# lab1_kuchenov_usb_spi.net
KiCad netlist of a schematic drawn in Altium Designer
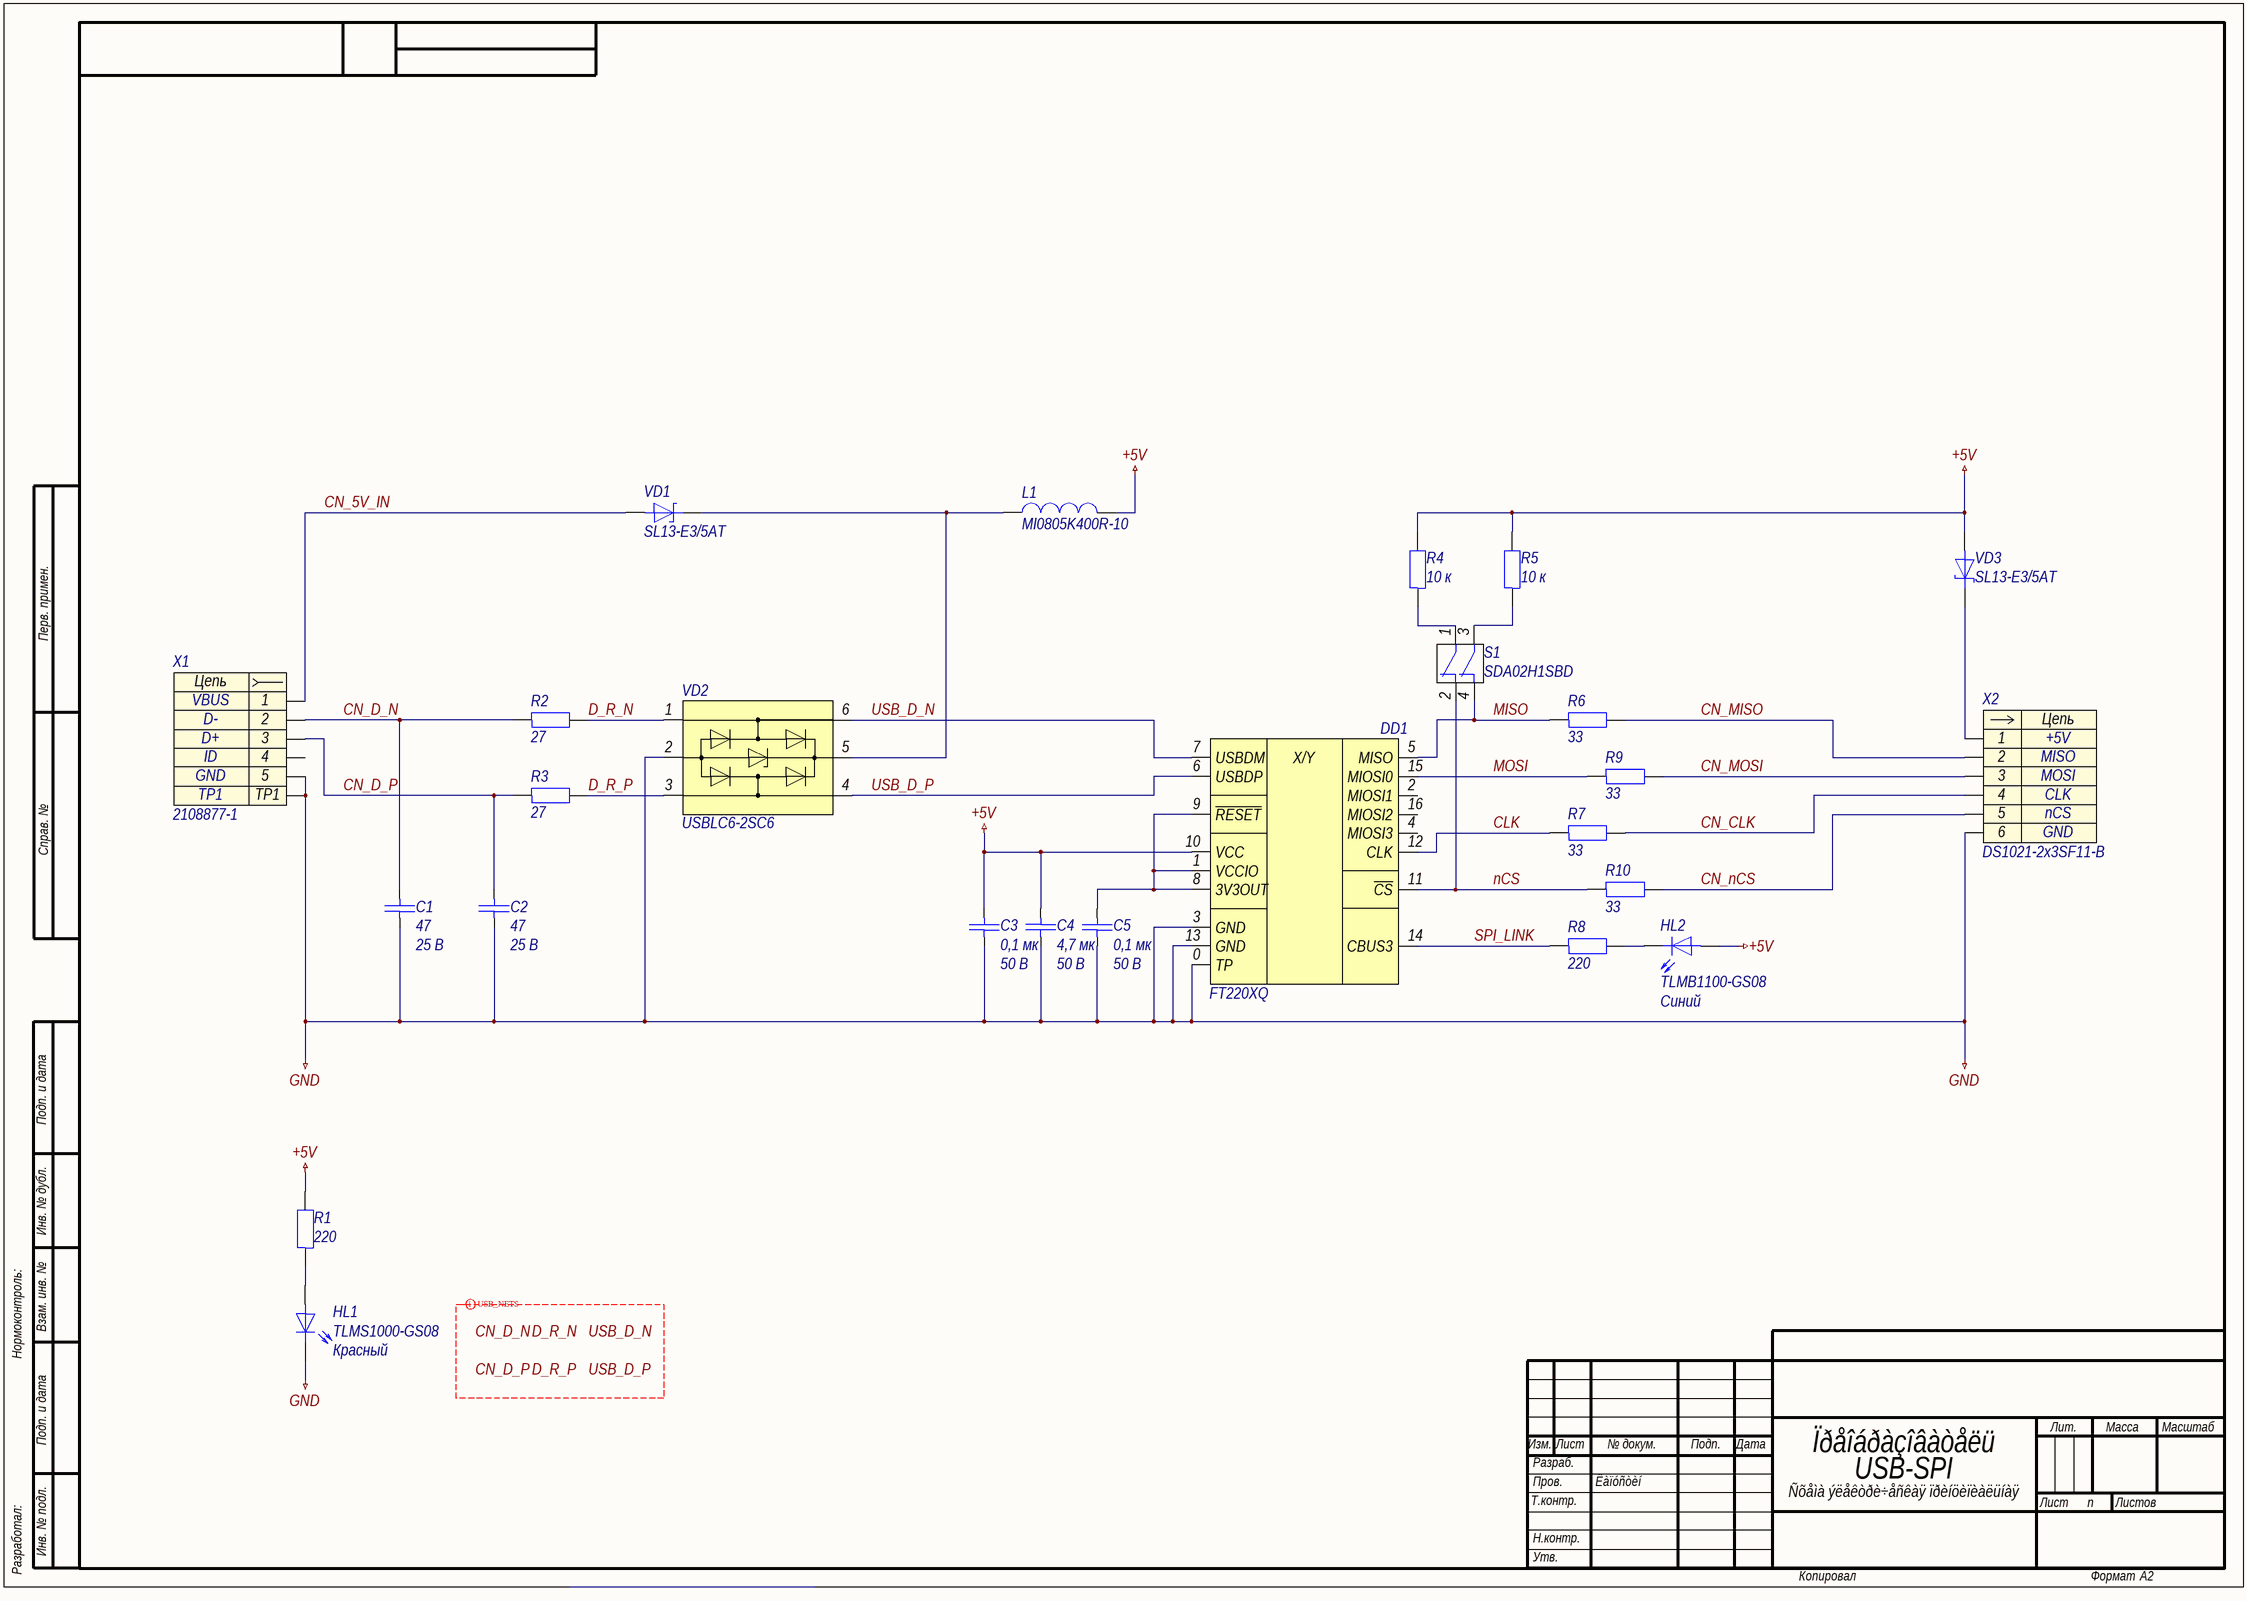
[diagram p0: lab1_kuchenov_usb_spi.SchDoc]

(export (version "E")
  (design (tool "Eeschema 10.0.6"))
  (components
    (comp (ref "C1")
      (value "47")
      (footprint "C0201")
      (description "=Описание")
      (fields (field (name "НАПРЯЖЕНИЕ") "25 В"))
      (libsource (lib "Database_Students") (part "CAPACITOR-NONPOLAR"))
    )
    (comp (ref "C2")
      (value "47")
      (footprint "C0201")
      (description "=Описание")
      (fields (field (name "НАПРЯЖЕНИЕ") "25 В"))
      (libsource (lib "Database_Students") (part "CAPACITOR-NONPOLAR"))
    )
    (comp (ref "C3")
      (value "0,1 мк")
      (footprint "C0603")
      (description "=Описание")
      (fields (field (name "НАПРЯЖЕНИЕ") "50 В"))
      (libsource (lib "Database_Students") (part "CAPACITOR-NONPOLAR"))
    )
    (comp (ref "C4")
      (value "4,7 мк")
      (footprint "C0805")
      (description "=Описание")
      (fields (field (name "НАПРЯЖЕНИЕ") "50 В"))
      (libsource (lib "Database_Students") (part "CAPACITOR-NONPOLAR"))
    )
    (comp (ref "C5")
      (value "0,1 мк")
      (footprint "C0603")
      (description "=Описание")
      (fields (field (name "НАПРЯЖЕНИЕ") "50 В"))
      (libsource (lib "Database_Students") (part "CAPACITOR-NONPOLAR"))
    )
    (comp (ref "DD1")
      (value "FT220XQ")
      (footprint "QFN-16-400X400X90")
      (description "=Описание")
      (libsource (lib "Database_Students") (part "FT220XQ"))
    )
    (comp (ref "HL1")
      (value "TLMS1000-GS08")
      (footprint "HL0603")
      (description "=Описание")
      (fields (field (name "COLOUR") "Красный"))
      (libsource (lib "Database_Students") (part "LED-COMMON"))
    )
    (comp (ref "HL2")
      (value "TLMB1100-GS08")
      (footprint "HL0603")
      (description "=Описание")
      (fields (field (name "COLOUR") "Синий"))
      (libsource (lib "Database_Students") (part "LED-COMMON"))
    )
    (comp (ref "L1")
      (value "MI0805K400R-10")
      (footprint "MI-2-0805")
      (description "=Описание")
      (libsource (lib "Database_Students") (part "FERRITE-BEAD"))
    )
    (comp (ref "R1")
      (value "220")
      (footprint "R0603")
      (description "=Описание")
      (libsource (lib "Database_Students") (part "R-COMMON"))
    )
    (comp (ref "R2")
      (value "27")
      (footprint "R0603")
      (description "=Описание")
      (libsource (lib "Database_Students") (part "R-COMMON"))
    )
    (comp (ref "R3")
      (value "27")
      (footprint "R0603")
      (description "=Описание")
      (libsource (lib "Database_Students") (part "R-COMMON"))
    )
    (comp (ref "R4")
      (value "10 к")
      (footprint "R0603")
      (description "=Описание")
      (libsource (lib "Database_Students") (part "R-COMMON"))
    )
    (comp (ref "R5")
      (value "10 к")
      (footprint "R0603")
      (description "=Описание")
      (libsource (lib "Database_Students") (part "R-COMMON"))
    )
    (comp (ref "R6")
      (value "33")
      (footprint "R0603")
      (description "=Описание")
      (libsource (lib "Database_Students") (part "R-COMMON"))
    )
    (comp (ref "R7")
      (value "33")
      (footprint "R0603")
      (description "=Описание")
      (libsource (lib "Database_Students") (part "R-COMMON"))
    )
    (comp (ref "R8")
      (value "220")
      (footprint "R0603")
      (description "=Описание")
      (libsource (lib "Database_Students") (part "R-COMMON"))
    )
    (comp (ref "R9")
      (value "33")
      (footprint "R0603")
      (description "=Описание")
      (libsource (lib "Database_Students") (part "R-COMMON"))
    )
    (comp (ref "R10")
      (value "33")
      (footprint "R0603")
      (description "=Описание")
      (libsource (lib "Database_Students") (part "R-COMMON"))
    )
    (comp (ref "S1")
      (value "SDA02H1SBD")
      (footprint "SDA02H1SBD")
      (description "=Описание")
      (libsource (lib "Database_Students") (part "SWITCH-4C"))
    )
    (comp (ref "VD1")
      (value "SL13-E3/5AT")
      (footprint "DO-214AC")
      (description "=Описание")
      (libsource (lib "Database_Students") (part "DIODE-SCHOTTKY"))
    )
    (comp (ref "VD2")
      (value "USBLC6-2SC6")
      (footprint "SOT23-6L")
      (description "=Описание")
      (libsource (lib "Database_Students") (part "USBLC6-2SC6"))
    )
    (comp (ref "VD3")
      (value "SL13-E3/5AT")
      (footprint "DO-214AC")
      (description "=Описание")
      (libsource (lib "Database_Students") (part "DIODE-SCHOTTKY"))
    )
    (comp (ref "X1")
      (value "2108877-1")
      (footprint "2108877-1")
      (libsource (lib "Database_Students") (part "HEADER-5-TP1-SCT"))
    )
    (comp (ref "X2")
      (value "DS1021-2x3SF11-B")
      (footprint "DS1021-2X3SF11-B")
      (description "=Описание")
      (libsource (lib "Database_Students") (part "HEADER-6-PLG"))
    )
  )
  (nets
    (net (code "1") (name "+5V") (class "Default")
      (node (ref "C3") (pin "1") (pinfunction "1_1") (pintype "passive"))
      (node (ref "C4") (pin "2") (pinfunction "2_2") (pintype "passive"))
      (node (ref "DD1") (pin "10") (pinfunction "VCC_10") (pintype "passive"))
      (node (ref "HL2") (pin "2") (pinfunction "2_2") (pintype "passive"))
      (node (ref "L1") (pin "2") (pinfunction "2_2") (pintype "passive"))
      (node (ref "R1") (pin "2") (pinfunction "2_2") (pintype "passive"))
      (node (ref "R4") (pin "2") (pinfunction "2_2") (pintype "passive"))
      (node (ref "R5") (pin "2") (pinfunction "2_2") (pintype "passive"))
      (node (ref "VD3") (pin "2") (pinfunction "2_2") (pintype "passive"))
    )
    (net (code "2") (name "/CLK") (class "Default")
      (node (ref "DD1") (pin "12") (pinfunction "CLK_12") (pintype "passive"))
      (node (ref "R7") (pin "1") (pinfunction "1_1") (pintype "passive"))
    )
    (net (code "3") (name "/CN_5V_IN") (class "Default")
      (node (ref "VD1") (pin "2") (pinfunction "2_2") (pintype "passive"))
      (node (ref "X1") (pin "1") (pinfunction "1_1") (pintype "passive"))
    )
    (net (code "4") (name "/CN_CLK") (class "Default")
      (node (ref "R7") (pin "2") (pinfunction "2_2") (pintype "passive"))
      (node (ref "X2") (pin "4") (pinfunction "4_4") (pintype "passive"))
    )
    (net (code "5") (name "/CN_D_N") (class "Default")
      (node (ref "C1") (pin "1") (pinfunction "1_1") (pintype "passive"))
      (node (ref "R2") (pin "1") (pinfunction "1_1") (pintype "passive"))
      (node (ref "X1") (pin "2") (pinfunction "2_2") (pintype "passive"))
    )
    (net (code "6") (name "/CN_D_P") (class "Default")
      (node (ref "C2") (pin "1") (pinfunction "1_1") (pintype "passive"))
      (node (ref "R3") (pin "1") (pinfunction "1_1") (pintype "passive"))
      (node (ref "X1") (pin "3") (pinfunction "3_3") (pintype "passive"))
    )
    (net (code "7") (name "/CN_MISO") (class "Default")
      (node (ref "R6") (pin "2") (pinfunction "2_2") (pintype "passive"))
      (node (ref "X2") (pin "2") (pinfunction "2_2") (pintype "passive"))
    )
    (net (code "8") (name "/CN_MOSI") (class "Default")
      (node (ref "R9") (pin "2") (pinfunction "2_2") (pintype "passive"))
      (node (ref "X2") (pin "3") (pinfunction "3_3") (pintype "passive"))
    )
    (net (code "9") (name "/CN_nCS") (class "Default")
      (node (ref "R10") (pin "2") (pinfunction "2_2") (pintype "passive"))
      (node (ref "X2") (pin "5") (pinfunction "5_5") (pintype "passive"))
    )
    (net (code "10") (name "/D_R_N") (class "Default")
      (node (ref "R2") (pin "2") (pinfunction "2_2") (pintype "passive"))
      (node (ref "VD2") (pin "1") (pinfunction "1_1") (pintype "passive"))
    )
    (net (code "11") (name "/D_R_P") (class "Default")
      (node (ref "R3") (pin "2") (pinfunction "2_2") (pintype "passive"))
      (node (ref "VD2") (pin "3") (pinfunction "3_3") (pintype "passive"))
    )
    (net (code "12") (name "/MISO") (class "Default")
      (node (ref "DD1") (pin "5") (pinfunction "MISO_5") (pintype "passive"))
      (node (ref "R6") (pin "1") (pinfunction "1_1") (pintype "passive"))
      (node (ref "S1") (pin "4") (pinfunction "4_4") (pintype "passive"))
    )
    (net (code "13") (name "/MOSI") (class "Default")
      (node (ref "DD1") (pin "15") (pinfunction "MIOSI0_15") (pintype "passive"))
      (node (ref "R9") (pin "1") (pinfunction "1_1") (pintype "passive"))
    )
    (net (code "14") (name "/SPI_LINK") (class "Default")
      (node (ref "DD1") (pin "14") (pinfunction "CBUS3_14") (pintype "passive"))
      (node (ref "R8") (pin "1") (pinfunction "1_1") (pintype "passive"))
    )
    (net (code "15") (name "/USB_D_N") (class "Default")
      (node (ref "DD1") (pin "7") (pinfunction "USBDM_7") (pintype "passive"))
      (node (ref "VD2") (pin "6") (pinfunction "6_6") (pintype "passive"))
    )
    (net (code "16") (name "/USB_D_P") (class "Default")
      (node (ref "DD1") (pin "6") (pinfunction "USBDP_6") (pintype "passive"))
      (node (ref "VD2") (pin "4") (pinfunction "4_4") (pintype "passive"))
    )
    (net (code "17") (name "/nCS") (class "Default")
      (node (ref "DD1") (pin "11") (pinfunction "~{CS}_11") (pintype "passive"))
      (node (ref "R10") (pin "1") (pinfunction "1_1") (pintype "passive"))
      (node (ref "S1") (pin "2") (pinfunction "2_2") (pintype "passive"))
    )
    (net (code "18") (name "GND") (class "Default")
      (node (ref "C1") (pin "2") (pinfunction "2_2") (pintype "passive"))
      (node (ref "C2") (pin "2") (pinfunction "2_2") (pintype "passive"))
      (node (ref "C3") (pin "2") (pinfunction "2_2") (pintype "passive"))
      (node (ref "C4") (pin "1") (pinfunction "1_1") (pintype "passive"))
      (node (ref "C5") (pin "2") (pinfunction "2_2") (pintype "passive"))
      (node (ref "DD1") (pin "0") (pinfunction "TP_0") (pintype "passive"))
      (node (ref "DD1") (pin "13") (pinfunction "GND_13") (pintype "passive"))
      (node (ref "DD1") (pin "3") (pinfunction "GND_3") (pintype "passive"))
      (node (ref "HL1") (pin "1") (pinfunction "1_1") (pintype "passive"))
      (node (ref "VD2") (pin "2") (pinfunction "2_2") (pintype "passive"))
      (node (ref "X1") (pin "5") (pinfunction "5_5") (pintype "passive"))
      (node (ref "X1") (pin "TP1") (pinfunction "TP1_TP1") (pintype "passive"))
      (node (ref "X2") (pin "6") (pinfunction "6_6") (pintype "passive"))
    )
    (net (code "19") (name "Net-(DD1-3V3OUT)") (class "Default")
      (node (ref "C5") (pin "1") (pinfunction "1_1") (pintype "passive"))
      (node (ref "DD1") (pin "1") (pinfunction "VCCIO_1") (pintype "passive"))
      (node (ref "DD1") (pin "8") (pinfunction "3V3OUT_8") (pintype "passive"))
      (node (ref "DD1") (pin "9") (pinfunction "~{RESET}_9") (pintype "passive"))
    )
    (net (code "20") (name "Net-(HL1-Pad2)") (class "Default")
      (node (ref "HL1") (pin "2") (pinfunction "2_2") (pintype "passive"))
      (node (ref "R1") (pin "1") (pinfunction "1_1") (pintype "passive"))
    )
    (net (code "21") (name "Net-(HL2-Pad1)") (class "Default")
      (node (ref "HL2") (pin "1") (pinfunction "1_1") (pintype "passive"))
      (node (ref "R8") (pin "2") (pinfunction "2_2") (pintype "passive"))
    )
    (net (code "22") (name "Net-(L1-Pad1)") (class "Default")
      (node (ref "L1") (pin "1") (pinfunction "1_1") (pintype "passive"))
      (node (ref "VD1") (pin "1") (pinfunction "1_1") (pintype "passive"))
      (node (ref "VD2") (pin "5") (pinfunction "5_5") (pintype "passive"))
    )
    (net (code "23") (name "Net-(R4-Pad1)") (class "Default")
      (node (ref "R4") (pin "1") (pinfunction "1_1") (pintype "passive"))
      (node (ref "S1") (pin "1") (pinfunction "1_1") (pintype "passive"))
    )
    (net (code "24") (name "Net-(R5-Pad1)") (class "Default")
      (node (ref "R5") (pin "1") (pinfunction "1_1") (pintype "passive"))
      (node (ref "S1") (pin "3") (pinfunction "3_3") (pintype "passive"))
    )
    (net (code "25") (name "Net-(VD3-Pad1)") (class "Default")
      (node (ref "VD3") (pin "1") (pinfunction "1_1") (pintype "passive"))
      (node (ref "X2") (pin "1") (pinfunction "1_1") (pintype "passive"))
    )
    (net (code "26") (name "unconnected-(DD1-MIOSI1-Pad2)") (class "Default")
      (node (ref "DD1") (pin "2") (pinfunction "MIOSI1_2") (pintype "passive"))
    )
    (net (code "27") (name "unconnected-(DD1-MIOSI2-Pad16)") (class "Default")
      (node (ref "DD1") (pin "16") (pinfunction "MIOSI2_16") (pintype "passive"))
    )
    (net (code "28") (name "unconnected-(DD1-MIOSI3-Pad4)") (class "Default")
      (node (ref "DD1") (pin "4") (pinfunction "MIOSI3_4") (pintype "passive"))
    )
    (net (code "29") (name "unconnected-(X1-Pad4)") (class "Default")
      (node (ref "X1") (pin "4") (pinfunction "4_4") (pintype "passive"))
    )
  )
)
